# WirelessMonitorSch.net
KiCad netlist of a schematic drawn in Altium Designer
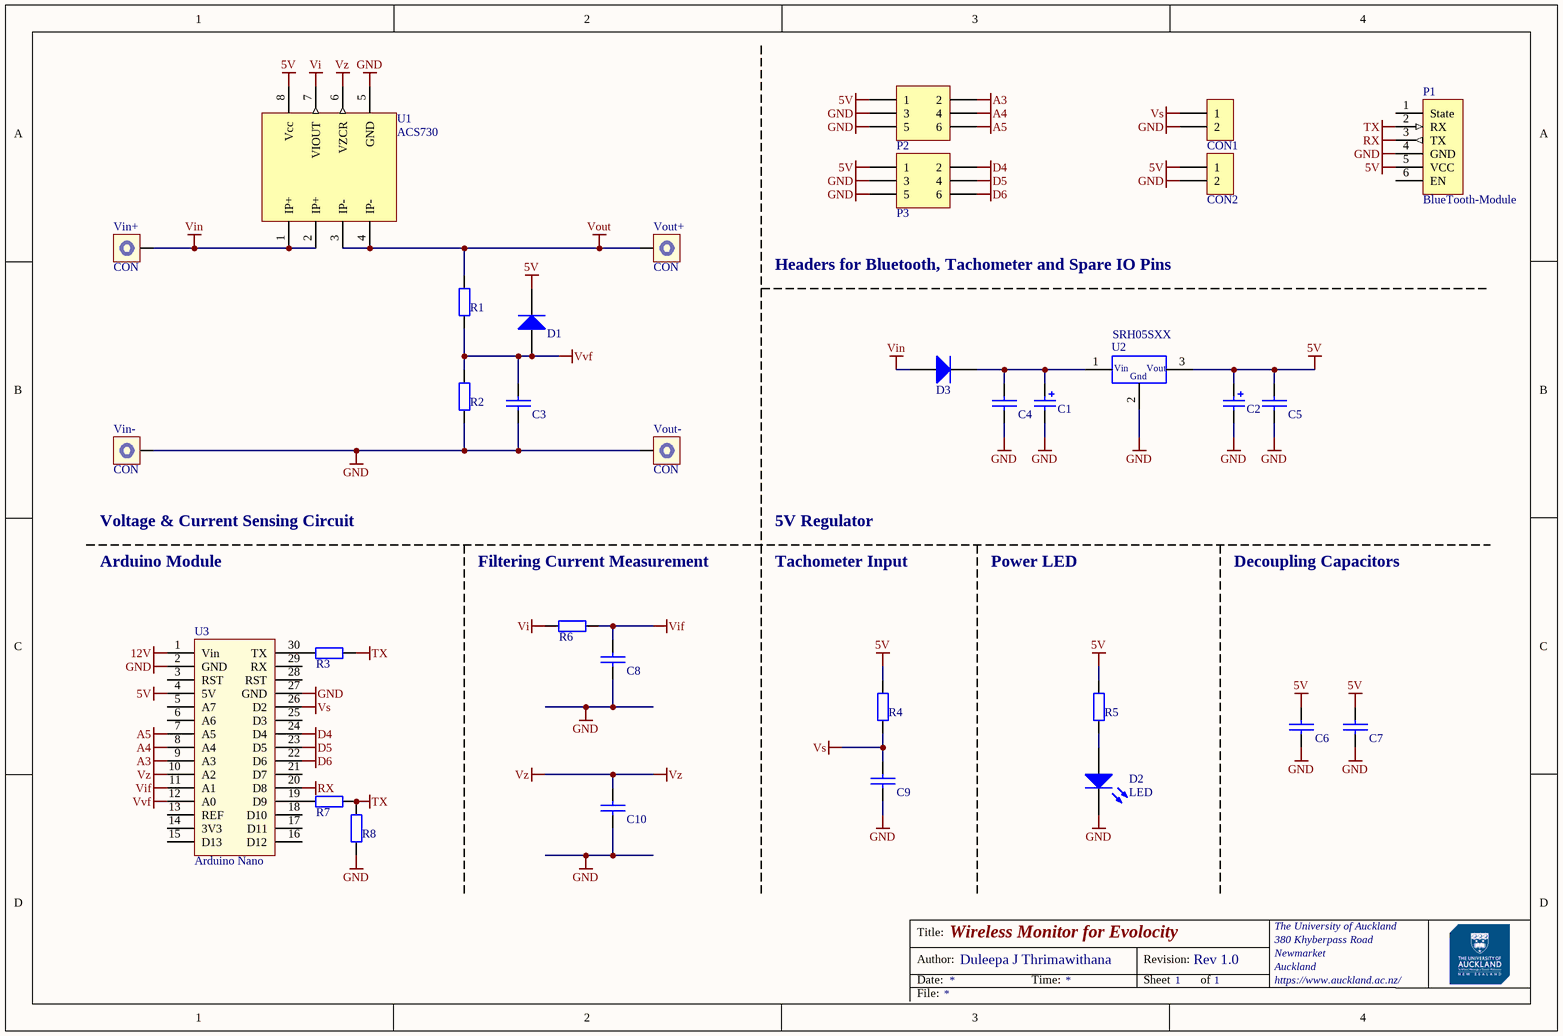
[diagram p0: WirelessMonitorSch.SchDoc]

(export (version "E")
  (design (tool "Eeschema 10.0.6"))
  (components
    (comp (ref "C1") (value "ECAP") (footprint "CR05") (libsource (lib "CommonDevices_V1") (part "ECAP")))
    (comp (ref "C2") (value "ECAP") (footprint "CR015") (libsource (lib "CommonDevices_V1") (part "ECAP")))
    (comp (ref "C3")
      (value "Film Cap")
      (footprint "CB05")
      (description "Film Cap Ax5")
      (libsource (lib "CommonDevices_V1") (part "FCAPAX5"))
    )
    (comp (ref "C4")
      (value "Film Cap")
      (footprint "CB05")
      (description "Film Cap Ax5")
      (libsource (lib "CommonDevices_V1") (part "FCAPAX5"))
    )
    (comp (ref "C5")
      (value "Film Cap")
      (footprint "CB05")
      (description "Film Cap Ax5")
      (libsource (lib "CommonDevices_V1") (part "FCAPAX5"))
    )
    (comp (ref "C6")
      (value "Film Cap")
      (footprint "CB05")
      (description "Film Cap Ax5")
      (libsource (lib "CommonDevices_V1") (part "FCAPAX5"))
    )
    (comp (ref "C7")
      (value "Film Cap")
      (footprint "CB05")
      (description "Film Cap Ax5")
      (libsource (lib "CommonDevices_V1") (part "FCAPAX5"))
    )
    (comp (ref "C8")
      (value "Film Cap")
      (footprint "CB05")
      (description "Film Cap Ax5")
      (libsource (lib "CommonDevices_V1") (part "FCAPAX5"))
    )
    (comp (ref "C9")
      (value "Film Cap")
      (footprint "CB05")
      (description "Film Cap Ax5")
      (libsource (lib "CommonDevices_V1") (part "FCAPAX5"))
    )
    (comp (ref "C10")
      (value "Film Cap")
      (footprint "CB05")
      (description "Film Cap Ax5")
      (libsource (lib "CommonDevices_V1") (part "FCAPAX5"))
    )
    (comp (ref "CON1")
      (value "Header 2X1")
      (footprint "HDR2X1_2P54")
      (libsource (lib "CommonDevices_V1") (part "HDR2X1"))
    )
    (comp (ref "CON2")
      (value "Header 2X1")
      (footprint "HDR2X1_2P54")
      (libsource (lib "CommonDevices_V1") (part "HDR2X1"))
    )
    (comp (ref "D1") (value "Diode") (footprint "DAX4") (libsource (lib "CommonDevices_V1") (part "Diode")))
    (comp (ref "D2") (value "LED") (footprint "LEDTH") (libsource (lib "CommonDevices_V1") (part "LED")))
    (comp (ref "D3") (value "Diode") (footprint "DAX4") (libsource (lib "CommonDevices_V1") (part "Diode")))
    (comp (ref "P1")
      (value "BlueTooth-Module")
      (footprint "HDRBLE")
      (description "Header, 6-Pin")
      (fields (field (name "PUBLISHER") "Altium Limited"))
      (libsource (lib "CommonDevices_V1") (part "HM10_Module"))
    )
    (comp (ref "P2")
      (value "HDR3X2")
      (footprint "HDR2X3_2P54")
      (description "Header, 3-Pin, Dual row")
      (libsource (lib "CommonDevices_V1") (part "HDR3X2"))
    )
    (comp (ref "P3")
      (value "HDR3X2")
      (footprint "HDR2X3_2P54")
      (description "Header, 3-Pin, Dual row")
      (libsource (lib "CommonDevices_V1") (part "HDR3X2"))
    )
    (comp (ref "R1")
      (value "Resistor")
      (footprint "RAX4")
      (description "Axial Resistor")
      (libsource (lib "CommonDevices_V1") (part "RESAX4"))
    )
    (comp (ref "R2")
      (value "Resistor")
      (footprint "RAX4")
      (description "Axial Resistor")
      (libsource (lib "CommonDevices_V1") (part "RESAX4"))
    )
    (comp (ref "R3")
      (value "Resistor")
      (footprint "RAX4")
      (description "Axial Resistor")
      (libsource (lib "") (part "RESAX4_1"))
    )
    (comp (ref "R4")
      (value "Resistor")
      (footprint "RAX4")
      (description "Axial Resistor")
      (libsource (lib "CommonDevices_V1") (part "RESAX4"))
    )
    (comp (ref "R5")
      (value "Resistor")
      (footprint "RAX4")
      (description "Axial Resistor")
      (libsource (lib "CommonDevices_V1") (part "RESAX4"))
    )
    (comp (ref "R6")
      (value "Resistor")
      (footprint "RAX4")
      (description "Axial Resistor")
      (libsource (lib "") (part "RESAX4_1"))
    )
    (comp (ref "R7")
      (value "Resistor")
      (footprint "RAX4")
      (description "Axial Resistor")
      (libsource (lib "") (part "RESAX4_1"))
    )
    (comp (ref "R8")
      (value "Resistor")
      (footprint "RAX4")
      (description "Axial Resistor")
      (libsource (lib "") (part "RESAX4_2"))
    )
    (comp (ref "U1")
      (value "ACS730")
      (footprint "SOIC8")
      (libsource (lib "CommonDevices_V1") (part "ACS730"))
    )
    (comp (ref "U2")
      (value "SRH05SXX")
      (footprint "SRH05")
      (description "SRH05 Series Wing Input Range Regulators")
      (libsource (lib "CommonDevices_V1") (part "SRH05SXX"))
    )
    (comp (ref "U3")
      (value "Arduino Nano")
      (footprint "ArduinoNano")
      (libsource (lib "CommonDevices_V1") (part "ArduinoNano"))
    )
    (comp (ref "Vin+")
      (value "CON")
      (footprint "CON_M3")
      (description "Term")
      (fields (field (name "PART NUMBER") "74651194R") (field (name "PUBLISHER") "Wurth Elektronik"))
      (libsource (lib "CommonDevices_V1") (part "Connector"))
    )
    (comp (ref "Vin-")
      (value "CON")
      (footprint "CON_M3")
      (description "Term")
      (fields (field (name "PART NUMBER") "74651194R") (field (name "PUBLISHER") "Wurth Elektronik"))
      (libsource (lib "CommonDevices_V1") (part "Connector"))
    )
    (comp (ref "Vout+")
      (value "CON")
      (footprint "CON_M3")
      (description "Term")
      (fields (field (name "PART NUMBER") "74651194R") (field (name "PUBLISHER") "Wurth Elektronik"))
      (libsource (lib "") (part "Connector_1"))
    )
    (comp (ref "Vout-")
      (value "CON")
      (footprint "CON_M3")
      (description "Term")
      (fields (field (name "PART NUMBER") "74651194R") (field (name "PUBLISHER") "Wurth Elektronik"))
      (libsource (lib "") (part "Connector_1"))
    )
  )
  (nets
    (net (code "1") (name "5V") (class "Default")
      (node (ref "C2") (pin "1") (pinfunction "1_1") (pintype "passive"))
      (node (ref "C5") (pin "2") (pinfunction "2_2") (pintype "passive"))
      (node (ref "C6") (pin "2") (pinfunction "2_2") (pintype "passive"))
      (node (ref "C7") (pin "2") (pinfunction "2_2") (pintype "passive"))
      (node (ref "CON2") (pin "1") (pinfunction "1_1") (pintype "passive"))
      (node (ref "D1") (pin "2") (pinfunction "2_2") (pintype "passive"))
      (node (ref "P1") (pin "5") (pinfunction "VCC_5") (pintype "power_in"))
      (node (ref "P2") (pin "1") (pinfunction "1_1") (pintype "passive"))
      (node (ref "P3") (pin "1") (pinfunction "1_1") (pintype "passive"))
      (node (ref "R4") (pin "2") (pinfunction "2_2") (pintype "passive"))
      (node (ref "R5") (pin "2") (pinfunction "2_2") (pintype "passive"))
      (node (ref "U1") (pin "8") (pinfunction "Vcc_8") (pintype "power_in"))
      (node (ref "U2") (pin "3") (pinfunction "Vout_3") (pintype "passive"))
      (node (ref "U3") (pin "4") (pinfunction "5V_4") (pintype "passive"))
    )
    (net (code "2") (name "12V") (class "Default")
      (node (ref "U3") (pin "1") (pinfunction "Vin_1") (pintype "passive"))
    )
    (net (code "3") (name "A3") (class "Default")
      (node (ref "P2") (pin "2") (pinfunction "2_2") (pintype "passive"))
      (node (ref "U3") (pin "9") (pinfunction "A3_9") (pintype "passive"))
    )
    (net (code "4") (name "A4") (class "Default")
      (node (ref "P2") (pin "4") (pinfunction "4_4") (pintype "passive"))
      (node (ref "U3") (pin "8") (pinfunction "A4_8") (pintype "passive"))
    )
    (net (code "5") (name "A5") (class "Default")
      (node (ref "P2") (pin "6") (pinfunction "6_6") (pintype "passive"))
      (node (ref "U3") (pin "7") (pinfunction "A5_7") (pintype "passive"))
    )
    (net (code "6") (name "D4") (class "Default")
      (node (ref "P3") (pin "2") (pinfunction "2_2") (pintype "passive"))
      (node (ref "U3") (pin "24") (pinfunction "D4_24") (pintype "passive"))
    )
    (net (code "7") (name "D5") (class "Default")
      (node (ref "P3") (pin "4") (pinfunction "4_4") (pintype "passive"))
      (node (ref "U3") (pin "23") (pinfunction "D5_23") (pintype "passive"))
    )
    (net (code "8") (name "D6") (class "Default")
      (node (ref "P3") (pin "6") (pinfunction "6_6") (pintype "passive"))
      (node (ref "U3") (pin "22") (pinfunction "D6_22") (pintype "passive"))
    )
    (net (code "9") (name "GND") (class "Default")
      (node (ref "C1") (pin "2") (pinfunction "2_2") (pintype "passive"))
      (node (ref "C10") (pin "1") (pinfunction "1_1") (pintype "passive"))
      (node (ref "C2") (pin "2") (pinfunction "2_2") (pintype "passive"))
      (node (ref "C3") (pin "1") (pinfunction "1_1") (pintype "passive"))
      (node (ref "C4") (pin "1") (pinfunction "1_1") (pintype "passive"))
      (node (ref "C5") (pin "1") (pinfunction "1_1") (pintype "passive"))
      (node (ref "C6") (pin "1") (pinfunction "1_1") (pintype "passive"))
      (node (ref "C7") (pin "1") (pinfunction "1_1") (pintype "passive"))
      (node (ref "C8") (pin "1") (pinfunction "1_1") (pintype "passive"))
      (node (ref "C9") (pin "1") (pinfunction "1_1") (pintype "passive"))
      (node (ref "CON1") (pin "2") (pinfunction "2_2") (pintype "passive"))
      (node (ref "CON2") (pin "2") (pinfunction "2_2") (pintype "passive"))
      (node (ref "D2") (pin "2") (pinfunction "K_2") (pintype "passive"))
      (node (ref "P1") (pin "4") (pinfunction "GND_4") (pintype "power_in"))
      (node (ref "P2") (pin "3") (pinfunction "3_3") (pintype "passive"))
      (node (ref "P2") (pin "5") (pinfunction "5_5") (pintype "passive"))
      (node (ref "P3") (pin "3") (pinfunction "3_3") (pintype "passive"))
      (node (ref "P3") (pin "5") (pinfunction "5_5") (pintype "passive"))
      (node (ref "R2") (pin "1") (pinfunction "1_1") (pintype "passive"))
      (node (ref "R8") (pin "2") (pinfunction "2_2") (pintype "passive"))
      (node (ref "U1") (pin "5") (pinfunction "GND_5") (pintype "power_in"))
      (node (ref "U2") (pin "2") (pinfunction "Gnd_2") (pintype "passive"))
      (node (ref "U3") (pin "2") (pinfunction "GND_2") (pintype "passive"))
      (node (ref "U3") (pin "27") (pinfunction "GND_27") (pintype "passive"))
      (node (ref "Vin-") (pin "1") (pinfunction "1_1") (pintype "passive"))
      (node (ref "Vout-") (pin "1") (pinfunction "1_1") (pintype "passive"))
    )
    (net (code "10") (name "Net-(D2-A)") (class "Default")
      (node (ref "D2") (pin "1") (pinfunction "A_1") (pintype "passive"))
      (node (ref "R5") (pin "1") (pinfunction "1_1") (pintype "passive"))
    )
    (net (code "11") (name "Net-(U2-Vin)") (class "Default")
      (node (ref "C1") (pin "1") (pinfunction "1_1") (pintype "passive"))
      (node (ref "C4") (pin "2") (pinfunction "2_2") (pintype "passive"))
      (node (ref "D3") (pin "2") (pinfunction "2_2") (pintype "passive"))
      (node (ref "U2") (pin "1") (pinfunction "Vin_1") (pintype "passive"))
    )
    (net (code "12") (name "Net-(U3-D9)") (class "Default")
      (node (ref "R7") (pin "2") (pinfunction "2_2") (pintype "passive"))
      (node (ref "U3") (pin "19") (pinfunction "D9_19") (pintype "passive"))
    )
    (net (code "13") (name "Net-(U3-TX)") (class "Default")
      (node (ref "R3") (pin "2") (pinfunction "2_2") (pintype "passive"))
      (node (ref "U3") (pin "30") (pinfunction "TX_30") (pintype "passive"))
    )
    (net (code "14") (name "RX") (class "Default")
      (node (ref "P1") (pin "3") (pinfunction "TX_3") (pintype "output"))
      (node (ref "U3") (pin "20") (pinfunction "D8_20") (pintype "passive"))
    )
    (net (code "15") (name "TX") (class "Default")
      (node (ref "P1") (pin "2") (pinfunction "RX_2") (pintype "input"))
      (node (ref "R3") (pin "1") (pinfunction "1_1") (pintype "passive"))
      (node (ref "R7") (pin "1") (pinfunction "1_1") (pintype "passive"))
      (node (ref "R8") (pin "1") (pinfunction "1_1") (pintype "passive"))
    )
    (net (code "16") (name "Vi") (class "Default")
      (node (ref "R6") (pin "2") (pinfunction "2_2") (pintype "passive"))
      (node (ref "U1") (pin "7") (pinfunction "VIOUT_7") (pintype "output"))
    )
    (net (code "17") (name "Vif") (class "Default")
      (node (ref "C8") (pin "2") (pinfunction "2_2") (pintype "passive"))
      (node (ref "R6") (pin "1") (pinfunction "1_1") (pintype "passive"))
      (node (ref "U3") (pin "11") (pinfunction "A1_11") (pintype "passive"))
    )
    (net (code "18") (name "Vin") (class "Default")
      (node (ref "D3") (pin "1") (pinfunction "1_1") (pintype "passive"))
      (node (ref "U1") (pin "1") (pinfunction "IP+_1") (pintype "passive"))
      (node (ref "U1") (pin "2") (pinfunction "IP+_2") (pintype "power_in"))
      (node (ref "Vin+") (pin "1") (pinfunction "1_1") (pintype "passive"))
    )
    (net (code "19") (name "Vout") (class "Default")
      (node (ref "R1") (pin "2") (pinfunction "2_2") (pintype "passive"))
      (node (ref "U1") (pin "3") (pinfunction "IP-_3") (pintype "power_in"))
      (node (ref "U1") (pin "4") (pinfunction "IP-_4") (pintype "passive"))
      (node (ref "Vout+") (pin "1") (pinfunction "1_1") (pintype "passive"))
    )
    (net (code "20") (name "Vs") (class "Default")
      (node (ref "C9") (pin "2") (pinfunction "2_2") (pintype "passive"))
      (node (ref "CON1") (pin "1") (pinfunction "1_1") (pintype "passive"))
      (node (ref "R4") (pin "1") (pinfunction "1_1") (pintype "passive"))
      (node (ref "U3") (pin "26") (pinfunction "D2_26") (pintype "passive"))
    )
    (net (code "21") (name "Vvf") (class "Default")
      (node (ref "C3") (pin "2") (pinfunction "2_2") (pintype "passive"))
      (node (ref "D1") (pin "1") (pinfunction "1_1") (pintype "passive"))
      (node (ref "R1") (pin "1") (pinfunction "1_1") (pintype "passive"))
      (node (ref "R2") (pin "2") (pinfunction "2_2") (pintype "passive"))
      (node (ref "U3") (pin "12") (pinfunction "A0_12") (pintype "passive"))
    )
    (net (code "22") (name "Vz") (class "Default")
      (node (ref "C10") (pin "2") (pinfunction "2_2") (pintype "passive"))
      (node (ref "U1") (pin "6") (pinfunction "VZCR_6") (pintype "output"))
      (node (ref "U3") (pin "10") (pinfunction "A2_10") (pintype "passive"))
    )
    (net (code "23") (name "unconnected-(P1-EN-Pad6)") (class "Default")
      (node (ref "P1") (pin "6") (pinfunction "EN_6") (pintype "passive"))
    )
    (net (code "24") (name "unconnected-(P1-State-Pad1)") (class "Default")
      (node (ref "P1") (pin "1") (pinfunction "State_1") (pintype "passive"))
    )
    (net (code "25") (name "unconnected-(U3-3V3-Pad14)") (class "Default")
      (node (ref "U3") (pin "14") (pinfunction "3V3_14") (pintype "passive"))
    )
    (net (code "26") (name "unconnected-(U3-A6-Pad6)") (class "Default")
      (node (ref "U3") (pin "6") (pinfunction "A6_6") (pintype "passive"))
    )
    (net (code "27") (name "unconnected-(U3-A7-Pad5)") (class "Default")
      (node (ref "U3") (pin "5") (pinfunction "A7_5") (pintype "passive"))
    )
    (net (code "28") (name "unconnected-(U3-D3-Pad25)") (class "Default")
      (node (ref "U3") (pin "25") (pinfunction "D3_25") (pintype "passive"))
    )
    (net (code "29") (name "unconnected-(U3-D7-Pad21)") (class "Default")
      (node (ref "U3") (pin "21") (pinfunction "D7_21") (pintype "passive"))
    )
    (net (code "30") (name "unconnected-(U3-D10-Pad18)") (class "Default")
      (node (ref "U3") (pin "18") (pinfunction "D10_18") (pintype "passive"))
    )
    (net (code "31") (name "unconnected-(U3-D11-Pad17)") (class "Default")
      (node (ref "U3") (pin "17") (pinfunction "D11_17") (pintype "passive"))
    )
    (net (code "32") (name "unconnected-(U3-D12-Pad16)") (class "Default")
      (node (ref "U3") (pin "16") (pinfunction "D12_16") (pintype "passive"))
    )
    (net (code "33") (name "unconnected-(U3-D13-Pad15)") (class "Default")
      (node (ref "U3") (pin "15") (pinfunction "D13_15") (pintype "passive"))
    )
    (net (code "34") (name "unconnected-(U3-REF-Pad13)") (class "Default")
      (node (ref "U3") (pin "13") (pinfunction "REF_13") (pintype "passive"))
    )
    (net (code "35") (name "unconnected-(U3-RST-Pad3)") (class "Default")
      (node (ref "U3") (pin "3") (pinfunction "RST_3") (pintype "passive"))
    )
    (net (code "36") (name "unconnected-(U3-RST-Pad28)") (class "Default")
      (node (ref "U3") (pin "28") (pinfunction "RST_28") (pintype "passive"))
    )
    (net (code "37") (name "unconnected-(U3-RX-Pad29)") (class "Default")
      (node (ref "U3") (pin "29") (pinfunction "RX_29") (pintype "passive"))
    )
  )
)
